# -_-.net
KiCad netlist of a schematic drawn in Altium Designer
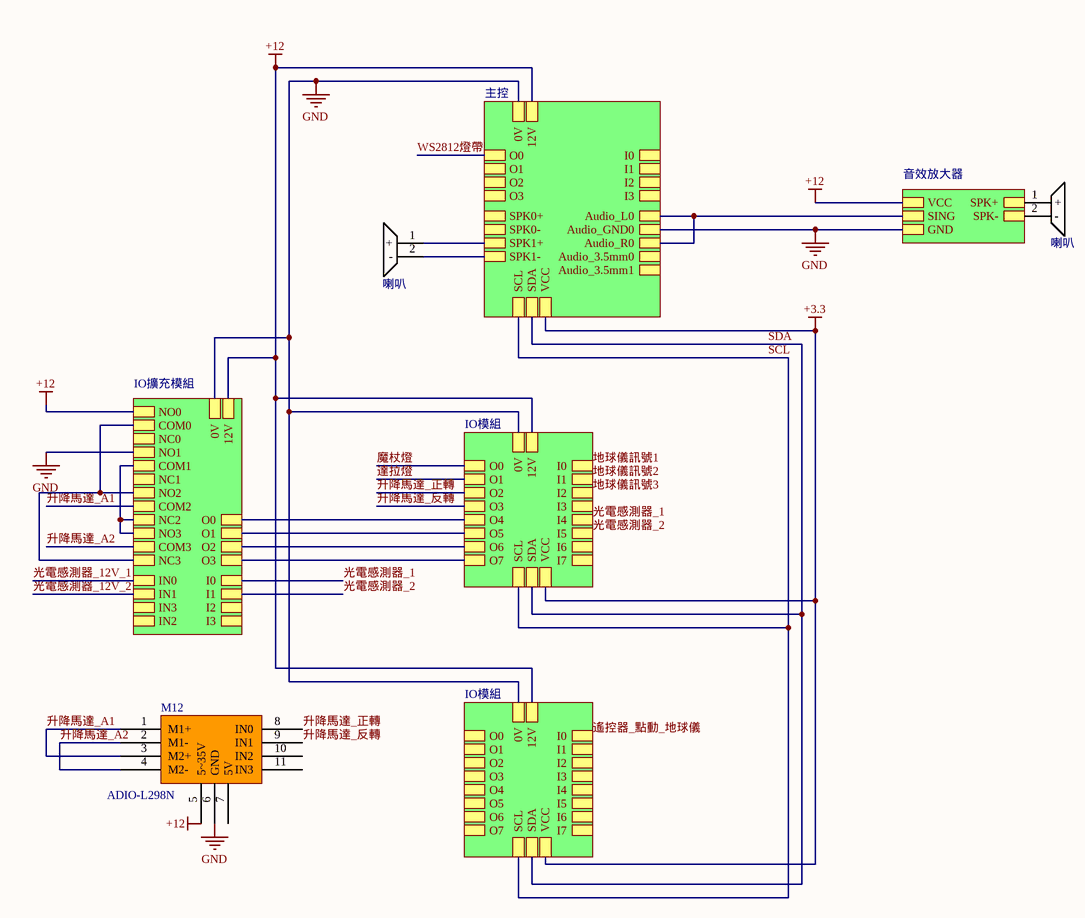
[diagram p0: 行天宮-流亡暗道-裂界裝置.SchDoc]

(export (version "E")
  (design (tool "Eeschema 10.0.6"))
  (components
    (comp (ref "B10")
      (value "喇叭")
      (footprint "Buzzer_12085")
      (description "無源蜂鳴器")
      (libsource (lib "MyLibray") (part "Buzzer"))
    )
    (comp (ref "B13")
      (value "喇叭")
      (footprint "Buzzer_12085")
      (description "無源蜂鳴器")
      (libsource (lib "MyLibray") (part "Buzzer"))
    )
    (comp (ref "M12")
      (value "ADIO-L298N")
      (footprint "L298N")
      (description "步進馬達控制、馬達正反轉模組")
      (libsource (lib "MyModule") (part "L298N"))
    )
  )
  (nets
    (net (code "2") (name "+12") (class "Default")
      (node (ref "M12") (pin "5") (pinfunction "5~35V_5") (pintype "passive"))
    )
    (net (code "45") (name "/SPK+") (class "Default")
      (node (ref "B10") (pin "1") (pinfunction "+_1") (pintype "passive"))
    )
    (net (code "46") (name "/SPK-") (class "Default")
      (node (ref "B10") (pin "2") (pinfunction "-_2") (pintype "passive"))
    )
    (net (code "49") (name "/SPK1+") (class "Default")
      (node (ref "B13") (pin "1") (pinfunction "+_1") (pintype "passive"))
    )
    (net (code "50") (name "/SPK1-") (class "Default")
      (node (ref "B13") (pin "2") (pinfunction "-_2") (pintype "passive"))
    )
    (net (code "56") (name "/升降馬達_A1") (class "Default")
      (node (ref "M12") (pin "1") (pinfunction "M1+_1") (pintype "passive"))
      (node (ref "M12") (pin "3") (pinfunction "M2+_3") (pintype "passive"))
    )
    (net (code "57") (name "/升降馬達_A2") (class "Default")
      (node (ref "M12") (pin "2") (pinfunction "M1-_2") (pintype "passive"))
      (node (ref "M12") (pin "4") (pinfunction "M2-_4") (pintype "passive"))
    )
    (net (code "58") (name "/升降馬達_反轉") (class "Default")
      (node (ref "M12") (pin "9") (pinfunction "IN1_9") (pintype "passive"))
    )
    (net (code "59") (name "/升降馬達_正轉") (class "Default")
      (node (ref "M12") (pin "8") (pinfunction "IN0_8") (pintype "passive"))
    )
    (net (code "66") (name "GND") (class "Default")
      (node (ref "M12") (pin "6") (pinfunction "GND_6") (pintype "passive"))
    )
    (net (code "67") (name "unconnected-(M12-5V-Pad7)") (class "Default")
      (node (ref "M12") (pin "7") (pinfunction "5V_7") (pintype "passive"))
    )
    (net (code "68") (name "unconnected-(M12-IN2-Pad10)") (class "Default")
      (node (ref "M12") (pin "10") (pinfunction "IN2_10") (pintype "passive"))
    )
    (net (code "69") (name "unconnected-(M12-IN3-Pad11)") (class "Default")
      (node (ref "M12") (pin "11") (pinfunction "IN3_11") (pintype "passive"))
    )
  )
)
